# uC_Board.net
KiCad netlist of a schematic drawn in Altium Designer
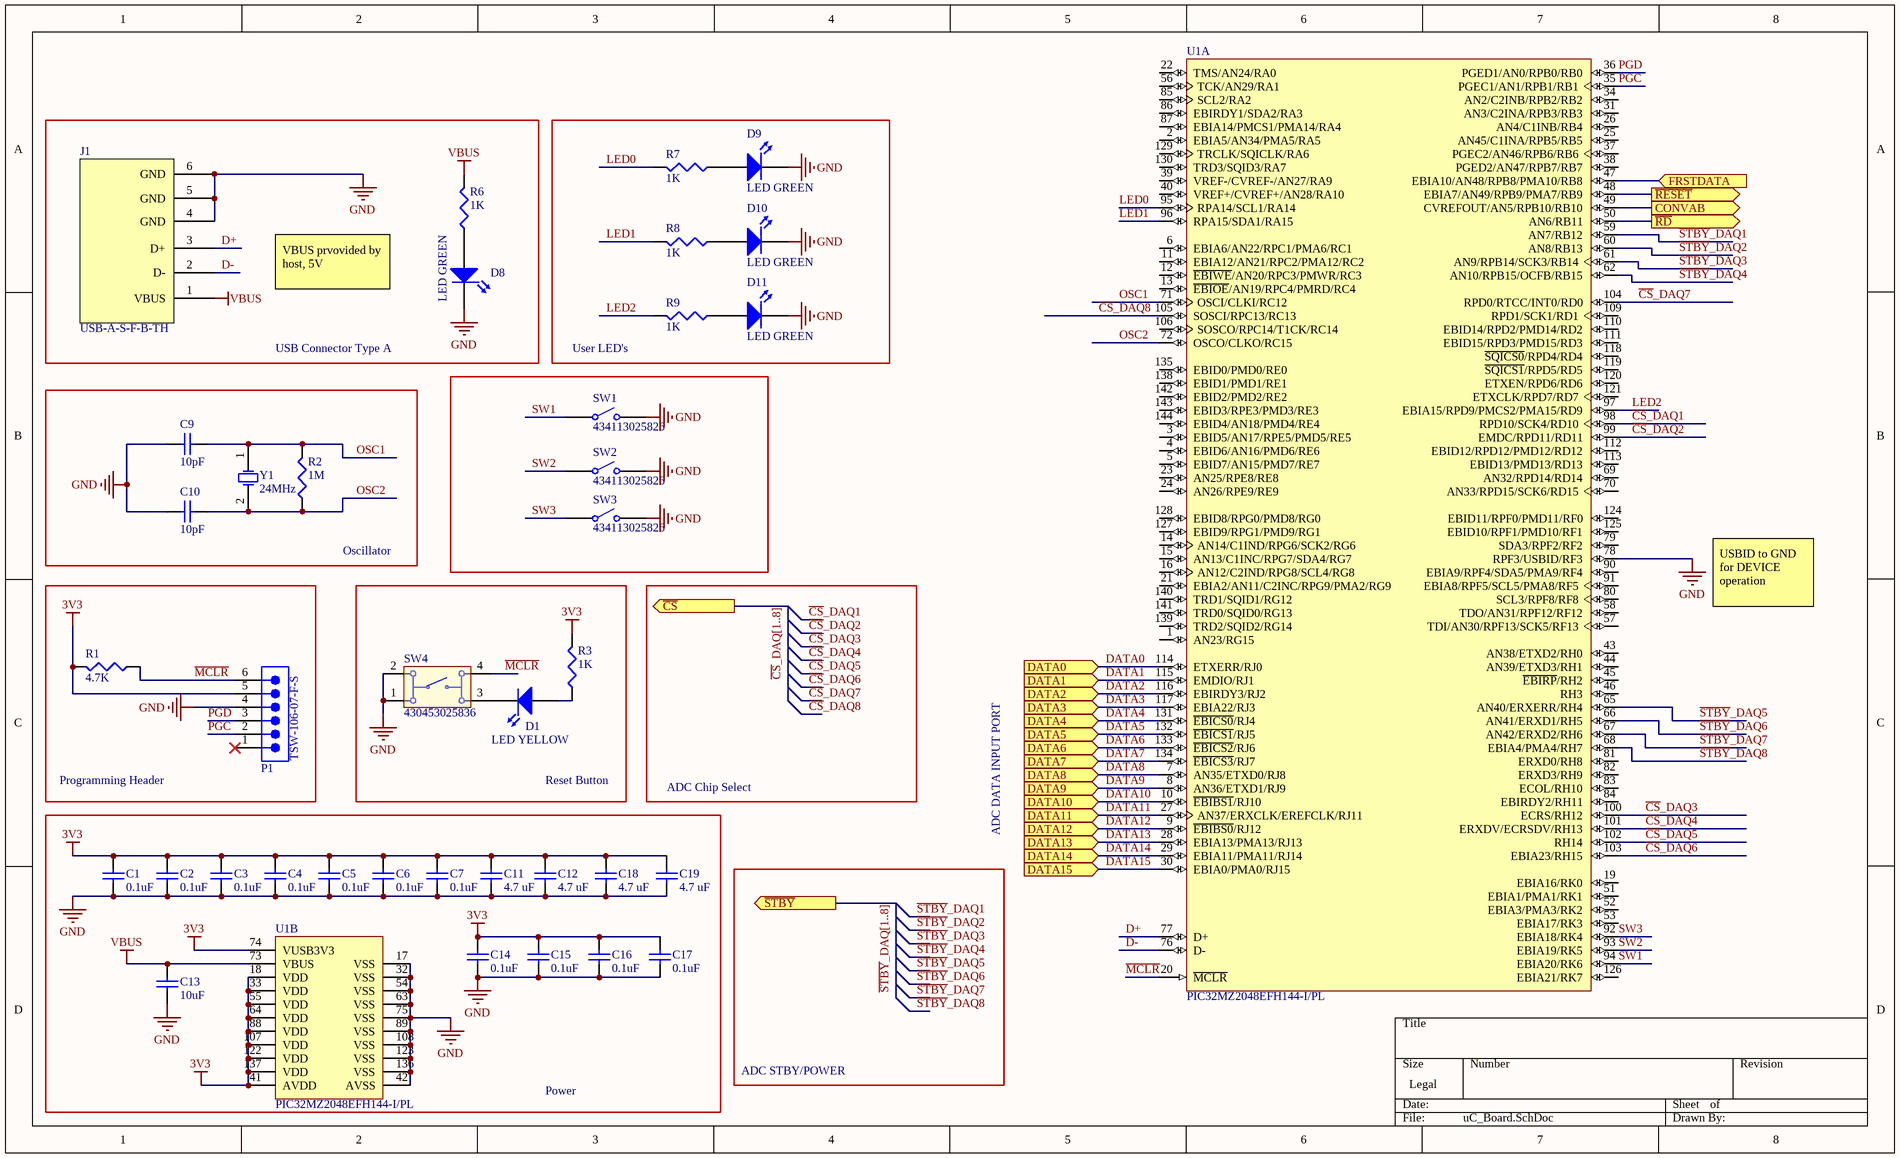
[diagram p0: uC_Board.SchDoc]

(export (version "E")
  (design (tool "Eeschema 10.0.6"))
  (components
    (comp (ref "C1")
      (value "0.1uF")
      (footprint "0402")
      (description "Ceramic Chip Capacitor - Standard")
      (fields (field (name "Comment") "C0402") (field (name "PUBLISHER") "Altium Limited"))
      (libsource (lib "KEMET Chip Capacitor") (part "C0402"))
    )
    (comp (ref "C2")
      (value "0.1uF")
      (footprint "0402")
      (description "Ceramic Chip Capacitor - Standard")
      (fields (field (name "Comment") "C0402") (field (name "PUBLISHER") "Altium Limited"))
      (libsource (lib "KEMET Chip Capacitor") (part "C0402"))
    )
    (comp (ref "C3")
      (value "0.1uF")
      (footprint "0402")
      (description "Ceramic Chip Capacitor - Standard")
      (fields (field (name "Comment") "C0402") (field (name "PUBLISHER") "Altium Limited"))
      (libsource (lib "KEMET Chip Capacitor") (part "C0402"))
    )
    (comp (ref "C4")
      (value "0.1uF")
      (footprint "0402")
      (description "Ceramic Chip Capacitor - Standard")
      (fields (field (name "Comment") "C0402") (field (name "PUBLISHER") "Altium Limited"))
      (libsource (lib "KEMET Chip Capacitor") (part "C0402"))
    )
    (comp (ref "C5")
      (value "0.1uF")
      (footprint "0402")
      (description "Ceramic Chip Capacitor - Standard")
      (fields (field (name "Comment") "C0402") (field (name "PUBLISHER") "Altium Limited"))
      (libsource (lib "KEMET Chip Capacitor") (part "C0402"))
    )
    (comp (ref "C6")
      (value "0.1uF")
      (footprint "0402")
      (description "Ceramic Chip Capacitor - Standard")
      (fields (field (name "Comment") "C0402") (field (name "PUBLISHER") "Altium Limited"))
      (libsource (lib "KEMET Chip Capacitor") (part "C0402"))
    )
    (comp (ref "C7")
      (value "0.1uF")
      (footprint "0402")
      (description "Ceramic Chip Capacitor - Standard")
      (fields (field (name "Comment") "C0402") (field (name "PUBLISHER") "Altium Limited"))
      (libsource (lib "KEMET Chip Capacitor") (part "C0402"))
    )
    (comp (ref "C9")
      (value "10pF")
      (footprint "0805")
      (description "Ceramic Chip Capacitor - Standard")
      (fields (field (name "Comment") "C0805") (field (name "PUBLISHER") "Altium Limited"))
      (libsource (lib "KEMET Chip Capacitor") (part "C0805"))
    )
    (comp (ref "C10")
      (value "10pF")
      (footprint "0805")
      (description "Ceramic Chip Capacitor - Standard")
      (fields (field (name "Comment") "C0805") (field (name "PUBLISHER") "Altium Limited"))
      (libsource (lib "KEMET Chip Capacitor") (part "C0805"))
    )
    (comp (ref "C11")
      (value "4.7 uF")
      (footprint "0603")
      (description "Ceramic Chip Capacitor - Standard")
      (fields (field (name "Comment") "C0603") (field (name "PUBLISHER") "Altium Limited"))
      (libsource (lib "KEMET Chip Capacitor") (part "C0603"))
    )
    (comp (ref "C12")
      (value "4.7 uF")
      (footprint "0603")
      (description "Ceramic Chip Capacitor - Standard")
      (fields (field (name "Comment") "C0603") (field (name "PUBLISHER") "Altium Limited"))
      (libsource (lib "KEMET Chip Capacitor") (part "C0603"))
    )
    (comp (ref "C13")
      (value "10uF")
      (footprint "0805")
      (description "Ceramic Chip Capacitor - Standard")
      (fields (field (name "Comment") "C0805") (field (name "PUBLISHER") "Altium Limited"))
      (libsource (lib "KEMET Chip Capacitor") (part "C0805"))
    )
    (comp (ref "C14")
      (value "0.1uF")
      (footprint "0402")
      (description "Ceramic Chip Capacitor - Standard")
      (fields (field (name "Comment") "C0402") (field (name "PUBLISHER") "Altium Limited"))
      (libsource (lib "KEMET Chip Capacitor") (part "C0402"))
    )
    (comp (ref "C15")
      (value "0.1uF")
      (footprint "0402")
      (description "Ceramic Chip Capacitor - Standard")
      (fields (field (name "Comment") "C0402") (field (name "PUBLISHER") "Altium Limited"))
      (libsource (lib "KEMET Chip Capacitor") (part "C0402"))
    )
    (comp (ref "C16")
      (value "0.1uF")
      (footprint "0402")
      (description "Ceramic Chip Capacitor - Standard")
      (fields (field (name "Comment") "C0402") (field (name "PUBLISHER") "Altium Limited"))
      (libsource (lib "KEMET Chip Capacitor") (part "C0402"))
    )
    (comp (ref "C17")
      (value "0.1uF")
      (footprint "0402")
      (description "Ceramic Chip Capacitor - Standard")
      (fields (field (name "Comment") "C0402") (field (name "PUBLISHER") "Altium Limited"))
      (libsource (lib "KEMET Chip Capacitor") (part "C0402"))
    )
    (comp (ref "C18")
      (value "4.7 uF")
      (footprint "0603")
      (description "Ceramic Chip Capacitor - Standard")
      (fields (field (name "Comment") "C0603") (field (name "PUBLISHER") "Altium Limited"))
      (libsource (lib "KEMET Chip Capacitor") (part "C0603"))
    )
    (comp (ref "C19")
      (value "4.7 uF")
      (footprint "0603")
      (description "Ceramic Chip Capacitor - Standard")
      (fields (field (name "Comment") "C0603") (field (name "PUBLISHER") "Altium Limited"))
      (libsource (lib "KEMET Chip Capacitor") (part "C0603"))
    )
    (comp (ref "D1")
      (value "LED YELLOW")
      (footprint "C0805")
      (description "Red LED; SMD 0805")
      (libsource (lib "CHIPS_Devices") (part "LED_YELLOW"))
    )
    (comp (ref "D8")
      (value "LED GREEN")
      (footprint "C0805")
      (description "Green LED; SMD 0805")
      (libsource (lib "CHIPS_Devices") (part "LED_GREEN"))
    )
    (comp (ref "D9")
      (value "LED GREEN")
      (footprint "C0805")
      (description "Green LED; SMD 0805")
      (libsource (lib "CHIPS_Devices") (part "LED_GREEN"))
    )
    (comp (ref "D10")
      (value "LED GREEN")
      (footprint "C0805")
      (description "Green LED; SMD 0805")
      (libsource (lib "CHIPS_Devices") (part "LED_GREEN"))
    )
    (comp (ref "D11")
      (value "LED GREEN")
      (footprint "C0805")
      (description "Green LED; SMD 0805")
      (libsource (lib "CHIPS_Devices") (part "LED_GREEN"))
    )
    (comp (ref "J1")
      (value "USB-A-S-F-B-TH")
      (footprint "USB-A Connector")
      (description "USB-A Connector- Through Hole")
      (libsource (lib "CHIPS_Devices") (part "USB-A Connector"))
    )
    (comp (ref "P1")
      (value "TSW-106-07-F-S")
      (footprint "SMTC-TSW-106-07-X-S")
      (description "0.025\" SQ Post Header, Through-hole, Vertical, -55 to 125 degC, 2.54 mm Pitch, 6-Pin, Male, RoHS")
      (fields (field (name "MANUFACTURER") "Samtec"))
      (libsource (lib "Samtec_2,54_mm_Pitch_Terminal_Strips") (part "TSW-106-07-F-S"))
    )
    (comp (ref "R1")
      (value "4.7K")
      (footprint "J1-0603")
      (description "Resistor")
      (fields (field (name "Comment") "Res3") (field (name "PUBLISHER") "Altium Limited"))
      (libsource (lib "Miscellaneous Devices") (part "Res3"))
    )
    (comp (ref "R2")
      (value "1M")
      (footprint "0402")
      (description "Resistor")
      (fields (field (name "Comment") "Res3") (field (name "PUBLISHER") "Altium Limited"))
      (libsource (lib "CHIPS_Devices") (part "Res3"))
    )
    (comp (ref "R3")
      (value "1K")
      (footprint "0402")
      (description "Resistor")
      (fields (field (name "Comment") "Res3") (field (name "PUBLISHER") "Altium Limited"))
      (libsource (lib "CHIPS_Devices") (part "Res3"))
    )
    (comp (ref "R6")
      (value "1K")
      (footprint "0402")
      (description "Resistor")
      (fields (field (name "Comment") "Res3") (field (name "PUBLISHER") "Altium Limited"))
      (libsource (lib "CHIPS_Devices") (part "Res3"))
    )
    (comp (ref "R7")
      (value "1K")
      (footprint "0402")
      (description "Resistor")
      (fields (field (name "Comment") "Res3") (field (name "PUBLISHER") "Altium Limited"))
      (libsource (lib "CHIPS_Devices") (part "Res3"))
    )
    (comp (ref "R8")
      (value "1K")
      (footprint "0402")
      (description "Resistor")
      (fields (field (name "Comment") "Res3") (field (name "PUBLISHER") "Altium Limited"))
      (libsource (lib "CHIPS_Devices") (part "Res3"))
    )
    (comp (ref "R9")
      (value "1K")
      (footprint "0402")
      (description "Resistor")
      (fields (field (name "Comment") "Res3") (field (name "PUBLISHER") "Altium Limited"))
      (libsource (lib "CHIPS_Devices") (part "Res3"))
    )
    (comp (ref "SW1")
      (value "434113025826")
      (footprint "434113025826")
      (description "WS-TASV J-Bend SMD Tact Switch 6.0X3.8 mm")
      (libsource (lib "WS-TASV J-Bend SMD Tact Switch 6.0X3.5 mm") (part "434113025826"))
    )
    (comp (ref "SW2")
      (value "434113025826")
      (footprint "434113025826")
      (description "WS-TASV J-Bend SMD Tact Switch 6.0X3.8 mm")
      (libsource (lib "WS-TASV J-Bend SMD Tact Switch 6.0X3.5 mm") (part "434113025826"))
    )
    (comp (ref "SW3")
      (value "434113025826")
      (footprint "434113025826")
      (description "WS-TASV J-Bend SMD Tact Switch 6.0X3.8 mm")
      (libsource (lib "WS-TASV J-Bend SMD Tact Switch 6.0X3.5 mm") (part "434113025826"))
    )
    (comp (ref "SW4")
      (value "430453025836")
      (footprint "430453025836")
      (description "WS-TASV J-Bend SMD Tact Switch 6X6 mm")
      (libsource (lib "WS-TASV J-Bend SMD Tact Switch 6X6 mm") (part "430453025836"))
    )
    (comp (ref "U1")
      (value "PIC32MZ2048EFH144-I/PL")
      (footprint "MCHP-LQFP-PL144_N")
      (fields (field (name "MANUFACTURER") "Microchip"))
      (libsource (lib "Microchip PIC32MZ") (part "PIC32MZ2048ECH144-I/PL"))
    )
    (comp (ref "Y1")
      (value "24MHz")
      (footprint "HC49US")
      (description "Crystal Oscillator")
      (fields (field (name "PUBLISHER") "Altium Limited"))
      (libsource (lib "CHIPS_Devices") (part "XTAL"))
    )
  )
  (nets
    (net (code "1") (name "/CONVAB") (class "Default")
      (node (ref "U1") (pin "49") (pinfunction "CVREFOUT/AN5/RPB10/RB10_49") (pintype "bidirectional"))
    )
    (net (code "2") (name "/D+") (class "Default")
      (node (ref "J1") (pin "3") (pinfunction "D+_3") (pintype "passive"))
      (node (ref "U1") (pin "77") (pinfunction "D+_77") (pintype "bidirectional"))
    )
    (net (code "3") (name "/D-") (class "Default")
      (node (ref "J1") (pin "2") (pinfunction "D-_2") (pintype "passive"))
      (node (ref "U1") (pin "76") (pinfunction "D-_76") (pintype "bidirectional"))
    )
    (net (code "4") (name "/DATA0") (class "Default")
      (node (ref "U1") (pin "114") (pinfunction "ETXERR/RJ0_114") (pintype "bidirectional"))
    )
    (net (code "5") (name "/DATA1") (class "Default")
      (node (ref "U1") (pin "115") (pinfunction "EMDIO/RJ1_115") (pintype "bidirectional"))
    )
    (net (code "6") (name "/DATA2") (class "Default")
      (node (ref "U1") (pin "116") (pinfunction "EBIRDY3/RJ2_116") (pintype "bidirectional"))
    )
    (net (code "7") (name "/DATA3") (class "Default")
      (node (ref "U1") (pin "117") (pinfunction "EBIA22/RJ3_117") (pintype "bidirectional"))
    )
    (net (code "8") (name "/DATA4") (class "Default")
      (node (ref "U1") (pin "131") (pinfunction "~{EBICS0}/RJ4_131") (pintype "bidirectional"))
    )
    (net (code "9") (name "/DATA5") (class "Default")
      (node (ref "U1") (pin "132") (pinfunction "~{EBICS1}/RJ5_132") (pintype "bidirectional"))
    )
    (net (code "10") (name "/DATA6") (class "Default")
      (node (ref "U1") (pin "133") (pinfunction "~{EBICS2}/RJ6_133") (pintype "bidirectional"))
    )
    (net (code "11") (name "/DATA7") (class "Default")
      (node (ref "U1") (pin "134") (pinfunction "~{EBICS3}/RJ7_134") (pintype "bidirectional"))
    )
    (net (code "12") (name "/DATA8") (class "Default")
      (node (ref "U1") (pin "7") (pinfunction "AN35/ETXD0/RJ8_7") (pintype "bidirectional"))
    )
    (net (code "13") (name "/DATA9") (class "Default")
      (node (ref "U1") (pin "8") (pinfunction "AN36/ETXD1/RJ9_8") (pintype "bidirectional"))
    )
    (net (code "14") (name "/DATA10") (class "Default")
      (node (ref "U1") (pin "10") (pinfunction "~{EBIBS1}/RJ10_10") (pintype "bidirectional"))
    )
    (net (code "15") (name "/DATA11") (class "Default")
      (node (ref "U1") (pin "27") (pinfunction "AN37/ERXCLK/EREFCLK/RJ11_27") (pintype "bidirectional"))
    )
    (net (code "16") (name "/DATA12") (class "Default")
      (node (ref "U1") (pin "9") (pinfunction "~{EBIBS0}/RJ12_9") (pintype "bidirectional"))
    )
    (net (code "17") (name "/DATA13") (class "Default")
      (node (ref "U1") (pin "28") (pinfunction "EBIA13/PMA13/RJ13_28") (pintype "bidirectional"))
    )
    (net (code "18") (name "/DATA14") (class "Default")
      (node (ref "U1") (pin "29") (pinfunction "EBIA11/PMA11/RJ14_29") (pintype "bidirectional"))
    )
    (net (code "19") (name "/DATA15") (class "Default")
      (node (ref "U1") (pin "30") (pinfunction "EBIA0/PMA0/RJ15_30") (pintype "bidirectional"))
    )
    (net (code "20") (name "/FRSTDATA") (class "Default")
      (node (ref "U1") (pin "47") (pinfunction "EBIA10/AN48/RPB8/PMA10/RB8_47") (pintype "bidirectional"))
    )
    (net (code "21") (name "/LED0") (class "Default")
      (node (ref "R7") (pin "2") (pinfunction "2_2") (pintype "passive"))
      (node (ref "U1") (pin "95") (pinfunction "RPA14/SCL1/RA14_95") (pintype "bidirectional"))
    )
    (net (code "22") (name "/LED1") (class "Default")
      (node (ref "R8") (pin "2") (pinfunction "2_2") (pintype "passive"))
      (node (ref "U1") (pin "96") (pinfunction "RPA15/SDA1/RA15_96") (pintype "bidirectional"))
    )
    (net (code "23") (name "/LED2") (class "Default")
      (node (ref "R9") (pin "2") (pinfunction "2_2") (pintype "passive"))
      (node (ref "U1") (pin "97") (pinfunction "EBIA15/RPD9/PMCS2/PMA15/RD9_97") (pintype "bidirectional"))
    )
    (net (code "24") (name "/OSC1") (class "Default")
      (node (ref "C9") (pin "2") (pinfunction "2_2") (pintype "passive"))
      (node (ref "R2") (pin "2") (pinfunction "2_2") (pintype "passive"))
      (node (ref "U1") (pin "71") (pinfunction "OSCI/CLKI/RC12_71") (pintype "bidirectional"))
      (node (ref "Y1") (pin "1") (pinfunction "OSC1_1") (pintype "passive"))
    )
    (net (code "25") (name "/OSC2") (class "Default")
      (node (ref "C10") (pin "2") (pinfunction "2_2") (pintype "passive"))
      (node (ref "R2") (pin "1") (pinfunction "1_1") (pintype "passive"))
      (node (ref "U1") (pin "72") (pinfunction "OSCO/CLKO/RC15_72") (pintype "bidirectional"))
      (node (ref "Y1") (pin "2") (pinfunction "OSC2_2") (pintype "passive"))
    )
    (net (code "26") (name "/PGC") (class "Default")
      (node (ref "P1") (pin "2") (pinfunction "2_2") (pintype "passive"))
      (node (ref "U1") (pin "35") (pinfunction "PGEC1/AN1/RPB1/RB1_35") (pintype "bidirectional"))
    )
    (net (code "27") (name "/PGD") (class "Default")
      (node (ref "P1") (pin "3") (pinfunction "3_3") (pintype "passive"))
      (node (ref "U1") (pin "36") (pinfunction "PGED1/AN0/RPB0/RB0_36") (pintype "bidirectional"))
    )
    (net (code "28") (name "/SW1") (class "Default")
      (node (ref "SW1") (pin "1") (pinfunction "1_1") (pintype "passive"))
      (node (ref "U1") (pin "94") (pinfunction "EBIA20/RK6_94") (pintype "bidirectional"))
    )
    (net (code "29") (name "/SW2") (class "Default")
      (node (ref "SW2") (pin "1") (pinfunction "1_1") (pintype "passive"))
      (node (ref "U1") (pin "93") (pinfunction "EBIA19/RK5_93") (pintype "bidirectional"))
    )
    (net (code "30") (name "/SW3") (class "Default")
      (node (ref "SW3") (pin "1") (pinfunction "1_1") (pintype "passive"))
      (node (ref "U1") (pin "92") (pinfunction "EBIA18/RK4_92") (pintype "bidirectional"))
    )
    (net (code "31") (name "/~{CS}_DAQ1") (class "Default")
      (node (ref "U1") (pin "98") (pinfunction "RPD10/SCK4/RD10_98") (pintype "bidirectional"))
    )
    (net (code "32") (name "/~{CS}_DAQ2") (class "Default")
      (node (ref "U1") (pin "99") (pinfunction "EMDC/RPD11/RD11_99") (pintype "bidirectional"))
    )
    (net (code "33") (name "/~{CS}_DAQ3") (class "Default")
      (node (ref "U1") (pin "100") (pinfunction "ECRS/RH12_100") (pintype "bidirectional"))
    )
    (net (code "34") (name "/~{CS}_DAQ4") (class "Default")
      (node (ref "U1") (pin "101") (pinfunction "ERXDV/ECRSDV/RH13_101") (pintype "bidirectional"))
    )
    (net (code "35") (name "/~{CS}_DAQ5") (class "Default")
      (node (ref "U1") (pin "102") (pinfunction "RH14_102") (pintype "bidirectional"))
    )
    (net (code "36") (name "/~{CS}_DAQ6") (class "Default")
      (node (ref "U1") (pin "103") (pinfunction "EBIA23/RH15_103") (pintype "bidirectional"))
    )
    (net (code "37") (name "/~{CS}_DAQ7") (class "Default")
      (node (ref "U1") (pin "104") (pinfunction "RPD0/RTCC/INT0/RD0_104") (pintype "bidirectional"))
    )
    (net (code "38") (name "/~{CS}_DAQ8") (class "Default")
      (node (ref "U1") (pin "105") (pinfunction "SOSCI/RPC13/RC13_105") (pintype "bidirectional"))
    )
    (net (code "40") (name "/~{MCLR}") (class "Default")
      (node (ref "P1") (pin "6") (pinfunction "6_6") (pintype "passive"))
      (node (ref "R1") (pin "1") (pinfunction "1_1") (pintype "passive"))
      (node (ref "SW4") (pin "4") (pinfunction "4_4") (pintype "passive"))
      (node (ref "U1") (pin "20") (pinfunction "~{MCLR}_20") (pintype "input"))
    )
    (net (code "41") (name "/~{RD}") (class "Default")
      (node (ref "U1") (pin "50") (pinfunction "AN6/RB11_50") (pintype "bidirectional"))
    )
    (net (code "42") (name "/~{RESET}") (class "Default")
      (node (ref "U1") (pin "48") (pinfunction "EBIA7/AN49/RPB9/PMA7/RB9_48") (pintype "bidirectional"))
    )
    (net (code "44") (name "/~{STBY}_DAQ1") (class "Default")
      (node (ref "U1") (pin "59") (pinfunction "AN7/RB12_59") (pintype "bidirectional"))
    )
    (net (code "45") (name "/~{STBY}_DAQ2") (class "Default")
      (node (ref "U1") (pin "60") (pinfunction "AN8/RB13_60") (pintype "bidirectional"))
    )
    (net (code "46") (name "/~{STBY}_DAQ3") (class "Default")
      (node (ref "U1") (pin "61") (pinfunction "AN9/RPB14/SCK3/RB14_61") (pintype "bidirectional"))
    )
    (net (code "47") (name "/~{STBY}_DAQ4") (class "Default")
      (node (ref "U1") (pin "62") (pinfunction "AN10/RPB15/OCFB/RB15_62") (pintype "bidirectional"))
    )
    (net (code "48") (name "/~{STBY}_DAQ5") (class "Default")
      (node (ref "U1") (pin "65") (pinfunction "AN40/ERXERR/RH4_65") (pintype "bidirectional"))
    )
    (net (code "49") (name "/~{STBY}_DAQ6") (class "Default")
      (node (ref "U1") (pin "66") (pinfunction "AN41/ERXD1/RH5_66") (pintype "bidirectional"))
    )
    (net (code "50") (name "/~{STBY}_DAQ7") (class "Default")
      (node (ref "U1") (pin "67") (pinfunction "AN42/ERXD2/RH6_67") (pintype "bidirectional"))
    )
    (net (code "51") (name "/~{STBY}_DAQ8") (class "Default")
      (node (ref "U1") (pin "68") (pinfunction "EBIA4/PMA4/RH7_68") (pintype "bidirectional"))
    )
    (net (code "53") (name "3V3") (class "Default")
      (node (ref "C1") (pin "2") (pinfunction "2_2") (pintype "passive"))
      (node (ref "C11") (pin "1") (pinfunction "1_1") (pintype "passive"))
      (node (ref "C12") (pin "1") (pinfunction "1_1") (pintype "passive"))
      (node (ref "C14") (pin "2") (pinfunction "2_2") (pintype "passive"))
      (node (ref "C15") (pin "2") (pinfunction "2_2") (pintype "passive"))
      (node (ref "C16") (pin "2") (pinfunction "2_2") (pintype "passive"))
      (node (ref "C17") (pin "2") (pinfunction "2_2") (pintype "passive"))
      (node (ref "C18") (pin "1") (pinfunction "1_1") (pintype "passive"))
      (node (ref "C19") (pin "1") (pinfunction "1_1") (pintype "passive"))
      (node (ref "C2") (pin "2") (pinfunction "2_2") (pintype "passive"))
      (node (ref "C3") (pin "2") (pinfunction "2_2") (pintype "passive"))
      (node (ref "C4") (pin "2") (pinfunction "2_2") (pintype "passive"))
      (node (ref "C5") (pin "2") (pinfunction "2_2") (pintype "passive"))
      (node (ref "C6") (pin "2") (pinfunction "2_2") (pintype "passive"))
      (node (ref "C7") (pin "2") (pinfunction "2_2") (pintype "passive"))
      (node (ref "P1") (pin "5") (pinfunction "5_5") (pintype "passive"))
      (node (ref "R1") (pin "2") (pinfunction "2_2") (pintype "passive"))
      (node (ref "R3") (pin "2") (pinfunction "2_2") (pintype "passive"))
      (node (ref "U1") (pin "107") (pinfunction "VDD_107") (pintype "power_in"))
      (node (ref "U1") (pin "122") (pinfunction "VDD_122") (pintype "power_in"))
      (node (ref "U1") (pin "137") (pinfunction "VDD_137") (pintype "power_in"))
      (node (ref "U1") (pin "18") (pinfunction "VDD_18") (pintype "power_in"))
      (node (ref "U1") (pin "33") (pinfunction "VDD_33") (pintype "power_in"))
      (node (ref "U1") (pin "41") (pinfunction "AVDD_41") (pintype "power_in"))
      (node (ref "U1") (pin "55") (pinfunction "VDD_55") (pintype "power_in"))
      (node (ref "U1") (pin "64") (pinfunction "VDD_64") (pintype "power_in"))
      (node (ref "U1") (pin "74") (pinfunction "VUSB3V3_74") (pintype "power_in"))
      (node (ref "U1") (pin "88") (pinfunction "VDD_88") (pintype "power_in"))
    )
    (net (code "54") (name "GND") (class "Default")
      (node (ref "C1") (pin "1") (pinfunction "1_1") (pintype "passive"))
      (node (ref "C10") (pin "1") (pinfunction "1_1") (pintype "passive"))
      (node (ref "C11") (pin "2") (pinfunction "2_2") (pintype "passive"))
      (node (ref "C12") (pin "2") (pinfunction "2_2") (pintype "passive"))
      (node (ref "C13") (pin "1") (pinfunction "1_1") (pintype "passive"))
      (node (ref "C14") (pin "1") (pinfunction "1_1") (pintype "passive"))
      (node (ref "C15") (pin "1") (pinfunction "1_1") (pintype "passive"))
      (node (ref "C16") (pin "1") (pinfunction "1_1") (pintype "passive"))
      (node (ref "C17") (pin "1") (pinfunction "1_1") (pintype "passive"))
      (node (ref "C18") (pin "2") (pinfunction "2_2") (pintype "passive"))
      (node (ref "C19") (pin "2") (pinfunction "2_2") (pintype "passive"))
      (node (ref "C2") (pin "1") (pinfunction "1_1") (pintype "passive"))
      (node (ref "C3") (pin "1") (pinfunction "1_1") (pintype "passive"))
      (node (ref "C4") (pin "1") (pinfunction "1_1") (pintype "passive"))
      (node (ref "C5") (pin "1") (pinfunction "1_1") (pintype "passive"))
      (node (ref "C6") (pin "1") (pinfunction "1_1") (pintype "passive"))
      (node (ref "C7") (pin "1") (pinfunction "1_1") (pintype "passive"))
      (node (ref "C9") (pin "1") (pinfunction "1_1") (pintype "passive"))
      (node (ref "D10") (pin "2") (pinfunction "K_2") (pintype "passive"))
      (node (ref "D11") (pin "2") (pinfunction "K_2") (pintype "passive"))
      (node (ref "D8") (pin "2") (pinfunction "K_2") (pintype "passive"))
      (node (ref "D9") (pin "2") (pinfunction "K_2") (pintype "passive"))
      (node (ref "J1") (pin "4") (pinfunction "GND_4") (pintype "passive"))
      (node (ref "J1") (pin "5") (pinfunction "GND_5") (pintype "passive"))
      (node (ref "J1") (pin "6") (pinfunction "GND_6") (pintype "passive"))
      (node (ref "P1") (pin "4") (pinfunction "4_4") (pintype "passive"))
      (node (ref "SW1") (pin "2") (pinfunction "2_2") (pintype "passive"))
      (node (ref "SW2") (pin "2") (pinfunction "2_2") (pintype "passive"))
      (node (ref "SW3") (pin "2") (pinfunction "2_2") (pintype "passive"))
      (node (ref "SW4") (pin "1") (pinfunction "1_1") (pintype "passive"))
      (node (ref "SW4") (pin "2") (pinfunction "2_2") (pintype "passive"))
      (node (ref "U1") (pin "108") (pinfunction "VSS_108") (pintype "power_in"))
      (node (ref "U1") (pin "123") (pinfunction "VSS_123") (pintype "power_in"))
      (node (ref "U1") (pin "136") (pinfunction "VSS_136") (pintype "power_in"))
      (node (ref "U1") (pin "17") (pinfunction "VSS_17") (pintype "power_in"))
      (node (ref "U1") (pin "32") (pinfunction "VSS_32") (pintype "power_in"))
      (node (ref "U1") (pin "42") (pinfunction "AVSS_42") (pintype "power_in"))
      (node (ref "U1") (pin "54") (pinfunction "VSS_54") (pintype "power_in"))
      (node (ref "U1") (pin "63") (pinfunction "VSS_63") (pintype "power_in"))
      (node (ref "U1") (pin "75") (pinfunction "VSS_75") (pintype "power_in"))
      (node (ref "U1") (pin "78") (pinfunction "RPF3/USBID/RF3_78") (pintype "bidirectional"))
      (node (ref "U1") (pin "89") (pinfunction "VSS_89") (pintype "power_in"))
    )
    (net (code "55") (name "Net-(D1-A)") (class "Default")
      (node (ref "D1") (pin "1") (pinfunction "A_1") (pintype "passive"))
      (node (ref "R3") (pin "1") (pinfunction "1_1") (pintype "passive"))
    )
    (net (code "56") (name "Net-(D1-K)") (class "Default")
      (node (ref "D1") (pin "2") (pinfunction "K_2") (pintype "passive"))
      (node (ref "SW4") (pin "3") (pinfunction "3_3") (pintype "passive"))
    )
    (net (code "57") (name "Net-(D8-A)") (class "Default")
      (node (ref "D8") (pin "1") (pinfunction "A_1") (pintype "passive"))
      (node (ref "R6") (pin "1") (pinfunction "1_1") (pintype "passive"))
    )
    (net (code "58") (name "Net-(D9-A)") (class "Default")
      (node (ref "D9") (pin "1") (pinfunction "A_1") (pintype "passive"))
      (node (ref "R7") (pin "1") (pinfunction "1_1") (pintype "passive"))
    )
    (net (code "59") (name "Net-(D10-A)") (class "Default")
      (node (ref "D10") (pin "1") (pinfunction "A_1") (pintype "passive"))
      (node (ref "R8") (pin "1") (pinfunction "1_1") (pintype "passive"))
    )
    (net (code "60") (name "Net-(D11-A)") (class "Default")
      (node (ref "D11") (pin "1") (pinfunction "A_1") (pintype "passive"))
      (node (ref "R9") (pin "1") (pinfunction "1_1") (pintype "passive"))
    )
    (net (code "61") (name "VBUS") (class "Default")
      (node (ref "C13") (pin "2") (pinfunction "2_2") (pintype "passive"))
      (node (ref "J1") (pin "1") (pinfunction "VBUS_1") (pintype "passive"))
      (node (ref "R6") (pin "2") (pinfunction "2_2") (pintype "passive"))
      (node (ref "U1") (pin "73") (pinfunction "VBUS_73") (pintype "power_in"))
    )
    (net (code "62") (name "unconnected-(P1-Pad1)") (class "Default")
      (node (ref "P1") (pin "1") (pinfunction "1_1") (pintype "passive+no_connect"))
    )
    (net (code "63") (name "unconnected-(U1A-AN2{slash}C2INB{slash}RPB2{slash}RB2-Pad34)") (class "Default")
      (node (ref "U1") (pin "34") (pinfunction "AN2/C2INB/RPB2/RB2_34") (pintype "bidirectional"))
    )
    (net (code "64") (name "unconnected-(U1A-AN3{slash}C2INA{slash}RPB3{slash}RB3-Pad31)") (class "Default")
      (node (ref "U1") (pin "31") (pinfunction "AN3/C2INA/RPB3/RB3_31") (pintype "bidirectional"))
    )
    (net (code "65") (name "unconnected-(U1A-AN4{slash}C1INB{slash}RB4-Pad26)") (class "Default")
      (node (ref "U1") (pin "26") (pinfunction "AN4/C1INB/RB4_26") (pintype "bidirectional"))
    )
    (net (code "66") (name "unconnected-(U1A-AN12{slash}C2IND{slash}RPG8{slash}SCL4{slash}RG8-Pad16)") (class "Default")
      (node (ref "U1") (pin "16") (pinfunction "AN12/C2IND/RPG8/SCL4/RG8_16") (pintype "bidirectional"))
    )
    (net (code "67") (name "unconnected-(U1A-AN13{slash}C1INC{slash}RPG7{slash}SDA4{slash}RG7-Pad15)") (class "Default")
      (node (ref "U1") (pin "15") (pinfunction "AN13/C1INC/RPG7/SDA4/RG7_15") (pintype "bidirectional"))
    )
    (net (code "68") (name "unconnected-(U1A-AN14{slash}C1IND{slash}RPG6{slash}SCK2{slash}RG6-Pad14)") (class "Default")
      (node (ref "U1") (pin "14") (pinfunction "AN14/C1IND/RPG6/SCK2/RG6_14") (pintype "bidirectional"))
    )
    (net (code "69") (name "unconnected-(U1A-AN23{slash}RG15-Pad1)") (class "Default")
      (node (ref "U1") (pin "1") (pinfunction "AN23/RG15_1") (pintype "bidirectional"))
    )
    (net (code "70") (name "unconnected-(U1A-AN25{slash}RPE8{slash}RE8-Pad23)") (class "Default")
      (node (ref "U1") (pin "23") (pinfunction "AN25/RPE8/RE8_23") (pintype "bidirectional"))
    )
    (net (code "71") (name "unconnected-(U1A-AN26{slash}RPE9{slash}RE9-Pad24)") (class "Default")
      (node (ref "U1") (pin "24") (pinfunction "AN26/RPE9/RE9_24") (pintype "bidirectional"))
    )
    (net (code "72") (name "unconnected-(U1A-AN32{slash}RPD14{slash}RD14-Pad69)") (class "Default")
      (node (ref "U1") (pin "69") (pinfunction "AN32/RPD14/RD14_69") (pintype "bidirectional"))
    )
    (net (code "73") (name "unconnected-(U1A-AN33{slash}RPD15{slash}SCK6{slash}RD15-Pad70)") (class "Default")
      (node (ref "U1") (pin "70") (pinfunction "AN33/RPD15/SCK6/RD15_70") (pintype "bidirectional"))
    )
    (net (code "74") (name "unconnected-(U1A-AN38{slash}ETXD2{slash}RH0-Pad43)") (class "Default")
      (node (ref "U1") (pin "43") (pinfunction "AN38/ETXD2/RH0_43") (pintype "bidirectional"))
    )
    (net (code "75") (name "unconnected-(U1A-AN39{slash}ETXD3{slash}RH1-Pad44)") (class "Default")
      (node (ref "U1") (pin "44") (pinfunction "AN39/ETXD3/RH1_44") (pintype "bidirectional"))
    )
    (net (code "76") (name "unconnected-(U1A-AN45{slash}C1INA{slash}RPB5{slash}RB5-Pad25)") (class "Default")
      (node (ref "U1") (pin "25") (pinfunction "AN45/C1INA/RPB5/RB5_25") (pintype "bidirectional"))
    )
    (net (code "77") (name "unconnected-(U1A-EBIA1{slash}PMA1{slash}RK1-Pad51)") (class "Default")
      (node (ref "U1") (pin "51") (pinfunction "EBIA1/PMA1/RK1_51") (pintype "bidirectional"))
    )
    (net (code "78") (name "unconnected-(U1A-EBIA2{slash}AN11{slash}C2INC{slash}RPG9{slash}PMA2{slash}RG9-Pad21)") (class "Default")
      (node (ref "U1") (pin "21") (pinfunction "EBIA2/AN11/C2INC/RPG9/PMA2/RG9_21") (pintype "bidirectional"))
    )
    (net (code "79") (name "unconnected-(U1A-EBIA3{slash}PMA3{slash}RK2-Pad52)") (class "Default")
      (node (ref "U1") (pin "52") (pinfunction "EBIA3/PMA3/RK2_52") (pintype "bidirectional"))
    )
    (net (code "80") (name "unconnected-(U1A-EBIA5{slash}AN34{slash}PMA5{slash}RA5-Pad2)") (class "Default")
      (node (ref "U1") (pin "2") (pinfunction "EBIA5/AN34/PMA5/RA5_2") (pintype "bidirectional"))
    )
    (net (code "81") (name "unconnected-(U1A-EBIA6{slash}AN22{slash}RPC1{slash}PMA6{slash}RC1-Pad6)") (class "Default")
      (node (ref "U1") (pin "6") (pinfunction "EBIA6/AN22/RPC1/PMA6/RC1_6") (pintype "bidirectional"))
    )
    (net (code "82") (name "unconnected-(U1A-EBIA8{slash}RPF5{slash}SCL5{slash}PMA8{slash}RF5-Pad91)") (class "Default")
      (node (ref "U1") (pin "91") (pinfunction "EBIA8/RPF5/SCL5/PMA8/RF5_91") (pintype "bidirectional"))
    )
    (net (code "83") (name "unconnected-(U1A-EBIA9{slash}RPF4{slash}SDA5{slash}PMA9{slash}RF4-Pad90)") (class "Default")
      (node (ref "U1") (pin "90") (pinfunction "EBIA9/RPF4/SDA5/PMA9/RF4_90") (pintype "bidirectional"))
    )
    (net (code "84") (name "unconnected-(U1A-EBIA12{slash}AN21{slash}RPC2{slash}PMA12{slash}RC2-Pad11)") (class "Default")
      (node (ref "U1") (pin "11") (pinfunction "EBIA12/AN21/RPC2/PMA12/RC2_11") (pintype "bidirectional"))
    )
    (net (code "85") (name "unconnected-(U1A-EBIA14{slash}PMCS1{slash}PMA14{slash}RA4-Pad87)") (class "Default")
      (node (ref "U1") (pin "87") (pinfunction "EBIA14/PMCS1/PMA14/RA4_87") (pintype "bidirectional"))
    )
    (net (code "86") (name "unconnected-(U1A-EBIA16{slash}RK0-Pad19)") (class "Default")
      (node (ref "U1") (pin "19") (pinfunction "EBIA16/RK0_19") (pintype "bidirectional"))
    )
    (net (code "87") (name "unconnected-(U1A-EBIA17{slash}RK3-Pad53)") (class "Default")
      (node (ref "U1") (pin "53") (pinfunction "EBIA17/RK3_53") (pintype "bidirectional"))
    )
    (net (code "88") (name "unconnected-(U1A-EBIA21{slash}RK7-Pad126)") (class "Default")
      (node (ref "U1") (pin "126") (pinfunction "EBIA21/RK7_126") (pintype "bidirectional"))
    )
    (net (code "89") (name "unconnected-(U1A-EBID0{slash}PMD0{slash}RE0-Pad135)") (class "Default")
      (node (ref "U1") (pin "135") (pinfunction "EBID0/PMD0/RE0_135") (pintype "bidirectional"))
    )
    (net (code "90") (name "unconnected-(U1A-EBID1{slash}PMD1{slash}RE1-Pad138)") (class "Default")
      (node (ref "U1") (pin "138") (pinfunction "EBID1/PMD1/RE1_138") (pintype "bidirectional"))
    )
    (net (code "91") (name "unconnected-(U1A-EBID2{slash}PMD2{slash}RE2-Pad142)") (class "Default")
      (node (ref "U1") (pin "142") (pinfunction "EBID2/PMD2/RE2_142") (pintype "bidirectional"))
    )
    (net (code "92") (name "unconnected-(U1A-EBID3{slash}RPE3{slash}PMD3{slash}RE3-Pad143)") (class "Default")
      (node (ref "U1") (pin "143") (pinfunction "EBID3/RPE3/PMD3/RE3_143") (pintype "bidirectional"))
    )
    (net (code "93") (name "unconnected-(U1A-EBID4{slash}AN18{slash}PMD4{slash}RE4-Pad144)") (class "Default")
      (node (ref "U1") (pin "144") (pinfunction "EBID4/AN18/PMD4/RE4_144") (pintype "bidirectional"))
    )
    (net (code "94") (name "unconnected-(U1A-EBID5{slash}AN17{slash}RPE5{slash}PMD5{slash}RE5-Pad3)") (class "Default")
      (node (ref "U1") (pin "3") (pinfunction "EBID5/AN17/RPE5/PMD5/RE5_3") (pintype "bidirectional"))
    )
    (net (code "95") (name "unconnected-(U1A-EBID6{slash}AN16{slash}PMD6{slash}RE6-Pad4)") (class "Default")
      (node (ref "U1") (pin "4") (pinfunction "EBID6/AN16/PMD6/RE6_4") (pintype "bidirectional"))
    )
    (net (code "96") (name "unconnected-(U1A-EBID7{slash}AN15{slash}PMD7{slash}RE7-Pad5)") (class "Default")
      (node (ref "U1") (pin "5") (pinfunction "EBID7/AN15/PMD7/RE7_5") (pintype "bidirectional"))
    )
    (net (code "97") (name "unconnected-(U1A-EBID8{slash}RPG0{slash}PMD8{slash}RG0-Pad128)") (class "Default")
      (node (ref "U1") (pin "128") (pinfunction "EBID8/RPG0/PMD8/RG0_128") (pintype "bidirectional"))
    )
    (net (code "98") (name "unconnected-(U1A-EBID9{slash}RPG1{slash}PMD9{slash}RG1-Pad127)") (class "Default")
      (node (ref "U1") (pin "127") (pinfunction "EBID9/RPG1/PMD9/RG1_127") (pintype "bidirectional"))
    )
    (net (code "99") (name "unconnected-(U1A-EBID10{slash}RPF1{slash}PMD10{slash}RF1-Pad125)") (class "Default")
      (node (ref "U1") (pin "125") (pinfunction "EBID10/RPF1/PMD10/RF1_125") (pintype "bidirectional"))
    )
    (net (code "100") (name "unconnected-(U1A-EBID11{slash}RPF0{slash}PMD11{slash}RF0-Pad124)") (class "Default")
      (node (ref "U1") (pin "124") (pinfunction "EBID11/RPF0/PMD11/RF0_124") (pintype "bidirectional"))
    )
    (net (code "101") (name "unconnected-(U1A-EBID12{slash}RPD12{slash}PMD12{slash}RD12-Pad112)") (class "Default")
      (node (ref "U1") (pin "112") (pinfunction "EBID12/RPD12/PMD12/RD12_112") (pintype "bidirectional"))
    )
    (net (code "102") (name "unconnected-(U1A-EBID13{slash}PMD13{slash}RD13-Pad113)") (class "Default")
      (node (ref "U1") (pin "113") (pinfunction "EBID13/PMD13/RD13_113") (pintype "bidirectional"))
    )
    (net (code "103") (name "unconnected-(U1A-EBID14{slash}RPD2{slash}PMD14{slash}RD2-Pad110)") (class "Default")
      (node (ref "U1") (pin "110") (pinfunction "EBID14/RPD2/PMD14/RD2_110") (pintype "bidirectional"))
    )
    (net (code "104") (name "unconnected-(U1A-EBID15{slash}RPD3{slash}PMD15{slash}RD3-Pad111)") (class "Default")
      (node (ref "U1") (pin "111") (pinfunction "EBID15/RPD3/PMD15/RD3_111") (pintype "bidirectional"))
    )
    (net (code "105") (name "unconnected-(U1A-EBIRDY1{slash}SDA2{slash}RA3-Pad86)") (class "Default")
      (node (ref "U1") (pin "86") (pinfunction "EBIRDY1/SDA2/RA3_86") (pintype "bidirectional"))
    )
    (net (code "106") (name "unconnected-(U1A-EBIRDY2{slash}RH11-Pad84)") (class "Default")
      (node (ref "U1") (pin "84") (pinfunction "EBIRDY2/RH11_84") (pintype "bidirectional"))
    )
    (net (code "107") (name "unconnected-(U1A-ECOL{slash}RH10-Pad83)") (class "Default")
      (node (ref "U1") (pin "83") (pinfunction "ECOL/RH10_83") (pintype "bidirectional"))
    )
    (net (code "108") (name "unconnected-(U1A-ERXD0{slash}RH8-Pad81)") (class "Default")
      (node (ref "U1") (pin "81") (pinfunction "ERXD0/RH8_81") (pintype "bidirectional"))
    )
    (net (code "109") (name "unconnected-(U1A-ERXD3{slash}RH9-Pad82)") (class "Default")
      (node (ref "U1") (pin "82") (pinfunction "ERXD3/RH9_82") (pintype "bidirectional"))
    )
    (net (code "110") (name "unconnected-(U1A-ETXCLK{slash}RPD7{slash}RD7-Pad121)") (class "Default")
      (node (ref "U1") (pin "121") (pinfunction "ETXCLK/RPD7/RD7_121") (pintype "bidirectional"))
    )
    (net (code "111") (name "unconnected-(U1A-ETXEN{slash}RPD6{slash}RD6-Pad120)") (class "Default")
      (node (ref "U1") (pin "120") (pinfunction "ETXEN/RPD6/RD6_120") (pintype "bidirectional"))
    )
    (net (code "112") (name "unconnected-(U1A-PGEC2{slash}AN46{slash}RPB6{slash}RB6-Pad37)") (class "Default")
      (node (ref "U1") (pin "37") (pinfunction "PGEC2/AN46/RPB6/RB6_37") (pintype "bidirectional"))
    )
    (net (code "113") (name "unconnected-(U1A-PGED2{slash}AN47{slash}RPB7{slash}RB7-Pad38)") (class "Default")
      (node (ref "U1") (pin "38") (pinfunction "PGED2/AN47/RPB7/RB7_38") (pintype "bidirectional"))
    )
    (net (code "114") (name "unconnected-(U1A-RH3-Pad46)") (class "Default")
      (node (ref "U1") (pin "46") (pinfunction "RH3_46") (pintype "bidirectional"))
    )
    (net (code "115") (name "unconnected-(U1A-RPD1{slash}SCK1{slash}RD1-Pad109)") (class "Default")
      (node (ref "U1") (pin "109") (pinfunction "RPD1/SCK1/RD1_109") (pintype "bidirectional"))
    )
    (net (code "116") (name "unconnected-(U1A-SCL2{slash}RA2-Pad85)") (class "Default")
      (node (ref "U1") (pin "85") (pinfunction "SCL2/RA2_85") (pintype "bidirectional"))
    )
    (net (code "117") (name "unconnected-(U1A-SCL3{slash}RPF8{slash}RF8-Pad80)") (class "Default")
      (node (ref "U1") (pin "80") (pinfunction "SCL3/RPF8/RF8_80") (pintype "bidirectional"))
    )
    (net (code "118") (name "unconnected-(U1A-SDA3{slash}RPF2{slash}RF2-Pad79)") (class "Default")
      (node (ref "U1") (pin "79") (pinfunction "SDA3/RPF2/RF2_79") (pintype "bidirectional"))
    )
    (net (code "119") (name "unconnected-(U1A-SOSCO{slash}RPC14{slash}T1CK{slash}RC14-Pad106)") (class "Default")
      (node (ref "U1") (pin "106") (pinfunction "SOSCO/RPC14/T1CK/RC14_106") (pintype "bidirectional"))
    )
    (net (code "120") (name "unconnected-(U1A-TCK{slash}AN29{slash}RA1-Pad56)") (class "Default")
      (node (ref "U1") (pin "56") (pinfunction "TCK/AN29/RA1_56") (pintype "bidirectional"))
    )
    (net (code "121") (name "unconnected-(U1A-TDI{slash}AN30{slash}RPF13{slash}SCK5{slash}RF13-Pad57)") (class "Default")
      (node (ref "U1") (pin "57") (pinfunction "TDI/AN30/RPF13/SCK5/RF13_57") (pintype "bidirectional"))
    )
    (net (code "122") (name "unconnected-(U1A-TDO{slash}AN31{slash}RPF12{slash}RF12-Pad58)") (class "Default")
      (node (ref "U1") (pin "58") (pinfunction "TDO/AN31/RPF12/RF12_58") (pintype "bidirectional"))
    )
    (net (code "123") (name "unconnected-(U1A-TMS{slash}AN24{slash}RA0-Pad22)") (class "Default")
      (node (ref "U1") (pin "22") (pinfunction "TMS/AN24/RA0_22") (pintype "bidirectional"))
    )
    (net (code "124") (name "unconnected-(U1A-TRCLK{slash}SQICLK{slash}RA6-Pad129)") (class "Default")
      (node (ref "U1") (pin "129") (pinfunction "TRCLK/SQICLK/RA6_129") (pintype "bidirectional"))
    )
    (net (code "125") (name "unconnected-(U1A-TRD0{slash}SQID0{slash}RG13-Pad141)") (class "Default")
      (node (ref "U1") (pin "141") (pinfunction "TRD0/SQID0/RG13_141") (pintype "bidirectional"))
    )
    (net (code "126") (name "unconnected-(U1A-TRD1{slash}SQID1{slash}RG12-Pad140)") (class "Default")
      (node (ref "U1") (pin "140") (pinfunction "TRD1/SQID1/RG12_140") (pintype "bidirectional"))
    )
    (net (code "127") (name "unconnected-(U1A-TRD2{slash}SQID2{slash}RG14-Pad139)") (class "Default")
      (node (ref "U1") (pin "139") (pinfunction "TRD2/SQID2/RG14_139") (pintype "bidirectional"))
    )
    (net (code "128") (name "unconnected-(U1A-TRD3{slash}SQID3{slash}RA7-Pad130)") (class "Default")
      (node (ref "U1") (pin "130") (pinfunction "TRD3/SQID3/RA7_130") (pintype "bidirectional"))
    )
    (net (code "129") (name "unconnected-(U1A-VREF+{slash}CVREF+{slash}AN28{slash}RA10-Pad40)") (class "Default")
      (node (ref "U1") (pin "40") (pinfunction "VREF+/CVREF+/AN28/RA10_40") (pintype "bidirectional"))
    )
    (net (code "130") (name "unconnected-(U1A-VREF-{slash}CVREF-{slash}AN27{slash}RA9-Pad39)") (class "Default")
      (node (ref "U1") (pin "39") (pinfunction "VREF-/CVREF-/AN27/RA9_39") (pintype "bidirectional"))
    )
    (net (code "131") (name "unconnected-(U1A-~{EBIOE}{slash}AN19{slash}RPC4{slash}PMRD{slash}RC4-Pad13)") (class "Default")
      (node (ref "U1") (pin "13") (pinfunction "~{EBIOE}/AN19/RPC4/PMRD/RC4_13") (pintype "bidirectional"))
    )
    (net (code "132") (name "unconnected-(U1A-~{EBIRP}{slash}RH2-Pad45)") (class "Default")
      (node (ref "U1") (pin "45") (pinfunction "~{EBIRP}/RH2_45") (pintype "bidirectional"))
    )
    (net (code "133") (name "unconnected-(U1A-~{EBIWE}{slash}AN20{slash}RPC3{slash}PMWR{slash}RC3-Pad12)") (class "Default")
      (node (ref "U1") (pin "12") (pinfunction "~{EBIWE}/AN20/RPC3/PMWR/RC3_12") (pintype "bidirectional"))
    )
    (net (code "134") (name "unconnected-(U1A-~{SQICS0}{slash}RPD4{slash}RD4-Pad118)") (class "Default")
      (node (ref "U1") (pin "118") (pinfunction "~{SQICS0}/RPD4/RD4_118") (pintype "bidirectional"))
    )
    (net (code "135") (name "unconnected-(U1A-~{SQICS1}{slash}RPD5{slash}RD5-Pad119)") (class "Default")
      (node (ref "U1") (pin "119") (pinfunction "~{SQICS1}/RPD5/RD5_119") (pintype "bidirectional"))
    )
  )
)
